# singleNode.net
KiCad netlist of a schematic drawn in EAGLE
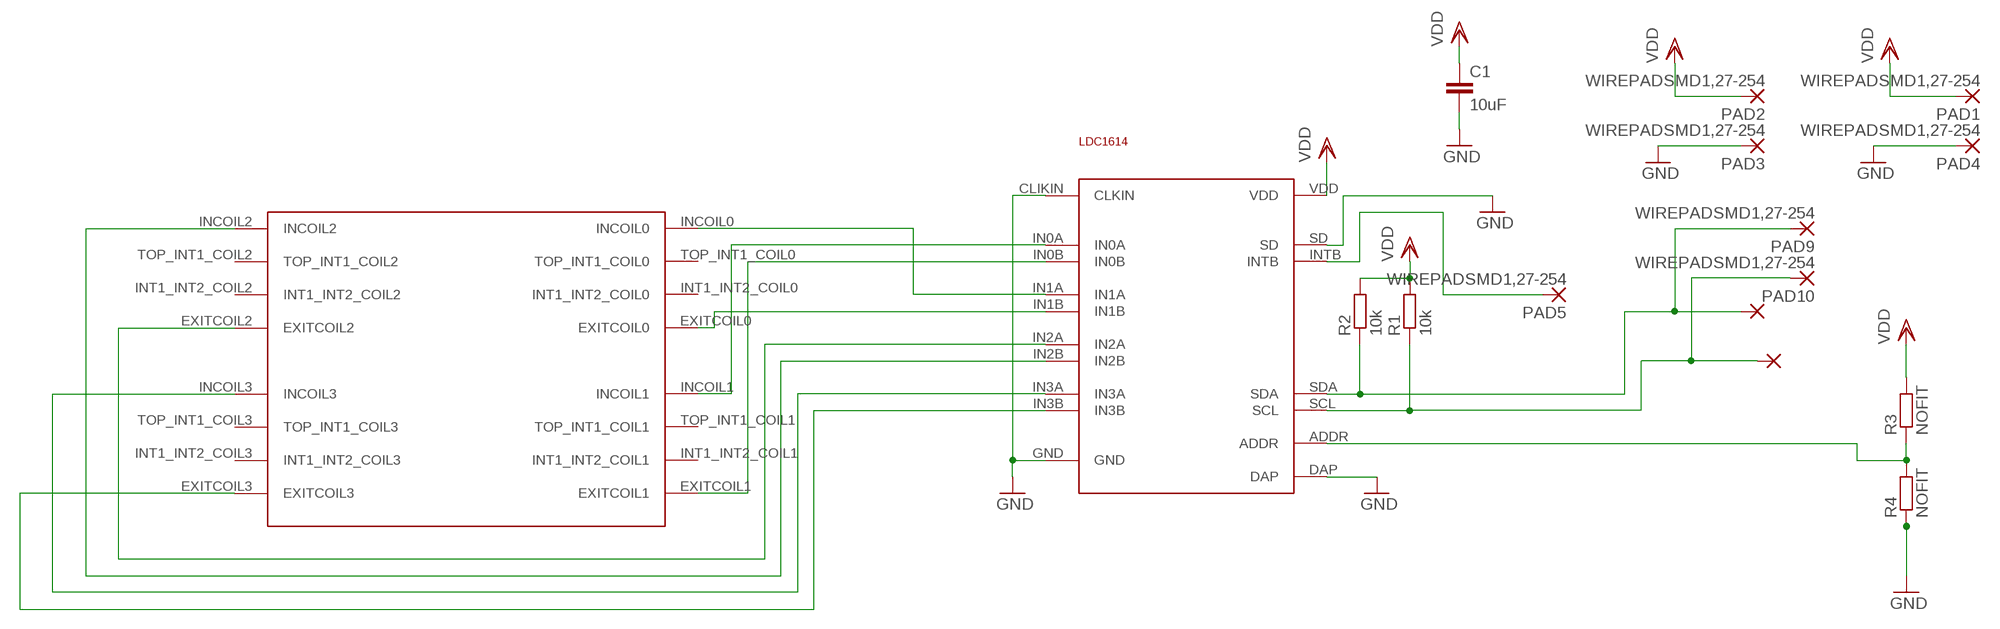
[diagram p0: schematic, sheet 1]

(export (version "E")
  (design (tool "Eeschema 10.0.6"))
  (components
    (comp (ref "C1")
      (value "10uF")
      (footprint "eagle-import:C0402")
      (libsource (lib "eagle-import") (part "C-EUC0402"))
    )
    (comp (ref "PAD1")
      (value "WIREPADSMD1,27-254")
      (footprint "eagle-import:SMD1,27-2,54")
      (libsource (lib "eagle-import") (part "WIREPADSMD1,27-254"))
    )
    (comp (ref "PAD2")
      (value "WIREPADSMD1,27-254")
      (footprint "eagle-import:SMD1,27-2,54")
      (libsource (lib "eagle-import") (part "WIREPADSMD1,27-254"))
    )
    (comp (ref "PAD3")
      (value "WIREPADSMD1,27-254")
      (footprint "eagle-import:SMD1,27-2,54")
      (libsource (lib "eagle-import") (part "WIREPADSMD1,27-254"))
    )
    (comp (ref "PAD4")
      (value "WIREPADSMD1,27-254")
      (footprint "eagle-import:SMD1,27-2,54")
      (libsource (lib "eagle-import") (part "WIREPADSMD1,27-254"))
    )
    (comp (ref "PAD5")
      (value "WIREPADSMD1,27-254")
      (footprint "eagle-import:SMD1,27-2,54")
      (libsource (lib "eagle-import") (part "WIREPADSMD1,27-254"))
    )
    (comp (ref "PAD6")
      (value "WIREPADSMD1,27-254")
      (footprint "eagle-import:SMD1,27-2,54")
      (libsource (lib "eagle-import") (part "WIREPADSMD1,27-254"))
    )
    (comp (ref "PAD7")
      (value "WIREPADSMD1,27-254")
      (footprint "eagle-import:SMD1,27-2,54")
      (libsource (lib "eagle-import") (part "WIREPADSMD1,27-254"))
    )
    (comp (ref "PAD9")
      (value "WIREPADSMD1,27-254")
      (footprint "eagle-import:SMD1,27-2,54")
      (libsource (lib "eagle-import") (part "WIREPADSMD1,27-254"))
    )
    (comp (ref "PAD10")
      (value "WIREPADSMD1,27-254")
      (footprint "eagle-import:SMD1,27-2,54")
      (libsource (lib "eagle-import") (part "WIREPADSMD1,27-254"))
    )
    (comp (ref "R1")
      (value "10k")
      (footprint "eagle-import:R0402")
      (libsource (lib "eagle-import") (part "R-EU_R0402"))
    )
    (comp (ref "R2")
      (value "10k")
      (footprint "eagle-import:R0402")
      (libsource (lib "eagle-import") (part "R-EU_R0402"))
    )
    (comp (ref "R3")
      (value "NOFIT")
      (footprint "eagle-import:R0201")
      (libsource (lib "eagle-import") (part "R-EU_R0201"))
    )
    (comp (ref "R4")
      (value "NOFIT")
      (footprint "eagle-import:R0201")
      (libsource (lib "eagle-import") (part "R-EU_R0201"))
    )
    (comp (ref "U$2")
      (value "FATSQUARE_GROUP")
      (footprint "eagle-import:FAT_SQUARE")
      (libsource (lib "eagle-import") (part "FATSQUARE_GROUP"))
    )
    (comp (ref "U1")
      (value "LDC1614")
      (footprint "eagle-import:WQFN-16")
      (libsource (lib "eagle-import") (part "LDC1614"))
    )
  )
  (nets
    (net (code "1") (name "GND") (class "Default")
      (node (ref "C1") (pin "2") (pinfunction "2_2") (pintype "passive"))
      (node (ref "PAD3") (pin "1") (pinfunction "P_1") (pintype "passive"))
      (node (ref "PAD4") (pin "1") (pinfunction "P_1") (pintype "passive"))
      (node (ref "R4") (pin "1") (pinfunction "1_1") (pintype "passive"))
      (node (ref "U1") (pin "CLIKIN") (pinfunction "CLKIN_CLIKIN") (pintype "bidirectional"))
      (node (ref "U1") (pin "DAP") (pinfunction "DAP_DAP") (pintype "bidirectional"))
      (node (ref "U1") (pin "GND") (pinfunction "GND_GND") (pintype "bidirectional"))
      (node (ref "U1") (pin "SD") (pinfunction "SD_SD") (pintype "bidirectional"))
    )
    (net (code "2") (name "Net-(PAD5-P)") (class "Default")
      (node (ref "PAD5") (pin "1") (pinfunction "P_1") (pintype "passive"))
      (node (ref "U1") (pin "INTB") (pinfunction "INTB_INTB") (pintype "bidirectional"))
    )
    (net (code "3") (name "Net-(PAD6-P)") (class "Default")
      (node (ref "PAD6") (pin "1") (pinfunction "P_1") (pintype "passive"))
      (node (ref "PAD9") (pin "1") (pinfunction "P_1") (pintype "passive"))
      (node (ref "R2") (pin "1") (pinfunction "1_1") (pintype "passive"))
      (node (ref "U1") (pin "SDA") (pinfunction "SDA_SDA") (pintype "bidirectional"))
    )
    (net (code "4") (name "Net-(PAD10-P)") (class "Default")
      (node (ref "PAD10") (pin "1") (pinfunction "P_1") (pintype "passive"))
      (node (ref "PAD7") (pin "1") (pinfunction "P_1") (pintype "passive"))
      (node (ref "R1") (pin "1") (pinfunction "1_1") (pintype "passive"))
      (node (ref "U1") (pin "SCL") (pinfunction "SCL_SCL") (pintype "bidirectional"))
    )
    (net (code "5") (name "Net-(R3-Pad1)") (class "Default")
      (node (ref "R3") (pin "1") (pinfunction "1_1") (pintype "passive"))
      (node (ref "R4") (pin "2") (pinfunction "2_2") (pintype "passive"))
      (node (ref "U1") (pin "ADDR") (pinfunction "ADDR_ADDR") (pintype "bidirectional"))
    )
    (net (code "6") (name "Net-(U$2-PadEXITCOIL0)") (class "Default")
      (node (ref "U$2") (pin "EXITCOIL0") (pinfunction "EXITCOIL0_EXITCOIL0") (pintype "bidirectional"))
      (node (ref "U1") (pin "IN1B") (pinfunction "IN1B_IN1B") (pintype "bidirectional"))
    )
    (net (code "7") (name "Net-(U$2-PadEXITCOIL1)") (class "Default")
      (node (ref "U$2") (pin "EXITCOIL1") (pinfunction "EXITCOIL1_EXITCOIL1") (pintype "bidirectional"))
      (node (ref "U1") (pin "IN0B") (pinfunction "IN0B_IN0B") (pintype "bidirectional"))
    )
    (net (code "8") (name "Net-(U$2-PadEXITCOIL2)") (class "Default")
      (node (ref "U$2") (pin "EXITCOIL2") (pinfunction "EXITCOIL2_EXITCOIL2") (pintype "bidirectional"))
      (node (ref "U1") (pin "IN2A") (pinfunction "IN2A_IN2A") (pintype "bidirectional"))
    )
    (net (code "9") (name "Net-(U$2-PadEXITCOIL3)") (class "Default")
      (node (ref "U$2") (pin "EXITCOIL3") (pinfunction "EXITCOIL3_EXITCOIL3") (pintype "bidirectional"))
      (node (ref "U1") (pin "IN3B") (pinfunction "IN3B_IN3B") (pintype "bidirectional"))
    )
    (net (code "10") (name "Net-(U$2-PadINCOIL0)") (class "Default")
      (node (ref "U$2") (pin "INCOIL0") (pinfunction "INCOIL0_INCOIL0") (pintype "bidirectional"))
      (node (ref "U1") (pin "IN1A") (pinfunction "IN1A_IN1A") (pintype "bidirectional"))
    )
    (net (code "11") (name "Net-(U$2-PadINCOIL1)") (class "Default")
      (node (ref "U$2") (pin "INCOIL1") (pinfunction "INCOIL1_INCOIL1") (pintype "bidirectional"))
      (node (ref "U1") (pin "IN0A") (pinfunction "IN0A_IN0A") (pintype "bidirectional"))
    )
    (net (code "12") (name "Net-(U$2-PadINCOIL2)") (class "Default")
      (node (ref "U$2") (pin "INCOIL2") (pinfunction "INCOIL2_INCOIL2") (pintype "bidirectional"))
      (node (ref "U1") (pin "IN2B") (pinfunction "IN2B_IN2B") (pintype "bidirectional"))
    )
    (net (code "13") (name "Net-(U$2-PadINCOIL3)") (class "Default")
      (node (ref "U$2") (pin "INCOIL3") (pinfunction "INCOIL3_INCOIL3") (pintype "bidirectional"))
      (node (ref "U1") (pin "IN3A") (pinfunction "IN3A_IN3A") (pintype "bidirectional"))
    )
    (net (code "14") (name "VDD") (class "Default")
      (node (ref "C1") (pin "1") (pinfunction "1_1") (pintype "passive"))
      (node (ref "PAD1") (pin "1") (pinfunction "P_1") (pintype "passive"))
      (node (ref "PAD2") (pin "1") (pinfunction "P_1") (pintype "passive"))
      (node (ref "R1") (pin "2") (pinfunction "2_2") (pintype "passive"))
      (node (ref "R2") (pin "2") (pinfunction "2_2") (pintype "passive"))
      (node (ref "R3") (pin "2") (pinfunction "2_2") (pintype "passive"))
      (node (ref "U1") (pin "VDD") (pinfunction "VDD_VDD") (pintype "bidirectional"))
    )
    (net (code "15") (name "unconnected-(U$2-PadINT1_INT2_COIL0)") (class "Default")
      (node (ref "U$2") (pin "INT1_INT2_COIL0") (pinfunction "INT1_INT2_COIL0_INT1_INT2_COIL0") (pintype "bidirectional"))
    )
    (net (code "16") (name "unconnected-(U$2-PadINT1_INT2_COIL1)") (class "Default")
      (node (ref "U$2") (pin "INT1_INT2_COIL1") (pinfunction "INT1_INT2_COIL1_INT1_INT2_COIL1") (pintype "bidirectional"))
    )
    (net (code "17") (name "unconnected-(U$2-PadINT1_INT2_COIL2)") (class "Default")
      (node (ref "U$2") (pin "INT1_INT2_COIL2") (pinfunction "INT1_INT2_COIL2_INT1_INT2_COIL2") (pintype "bidirectional"))
    )
    (net (code "18") (name "unconnected-(U$2-PadINT1_INT2_COIL3)") (class "Default")
      (node (ref "U$2") (pin "INT1_INT2_COIL3") (pinfunction "INT1_INT2_COIL3_INT1_INT2_COIL3") (pintype "bidirectional"))
    )
    (net (code "19") (name "unconnected-(U$2-PadTOP_INT1_COIL0)") (class "Default")
      (node (ref "U$2") (pin "TOP_INT1_COIL0") (pinfunction "TOP_INT1_COIL0_TOP_INT1_COIL0") (pintype "bidirectional"))
    )
    (net (code "20") (name "unconnected-(U$2-PadTOP_INT1_COIL1)") (class "Default")
      (node (ref "U$2") (pin "TOP_INT1_COIL1") (pinfunction "TOP_INT1_COIL1_TOP_INT1_COIL1") (pintype "bidirectional"))
    )
    (net (code "21") (name "unconnected-(U$2-PadTOP_INT1_COIL2)") (class "Default")
      (node (ref "U$2") (pin "TOP_INT1_COIL2") (pinfunction "TOP_INT1_COIL2_TOP_INT1_COIL2") (pintype "bidirectional"))
    )
    (net (code "22") (name "unconnected-(U$2-PadTOP_INT1_COIL3)") (class "Default")
      (node (ref "U$2") (pin "TOP_INT1_COIL3") (pinfunction "TOP_INT1_COIL3_TOP_INT1_COIL3") (pintype "bidirectional"))
    )
  )
)
